# MiniRelay.net
KiCad netlist of a schematic drawn in Altium Designer
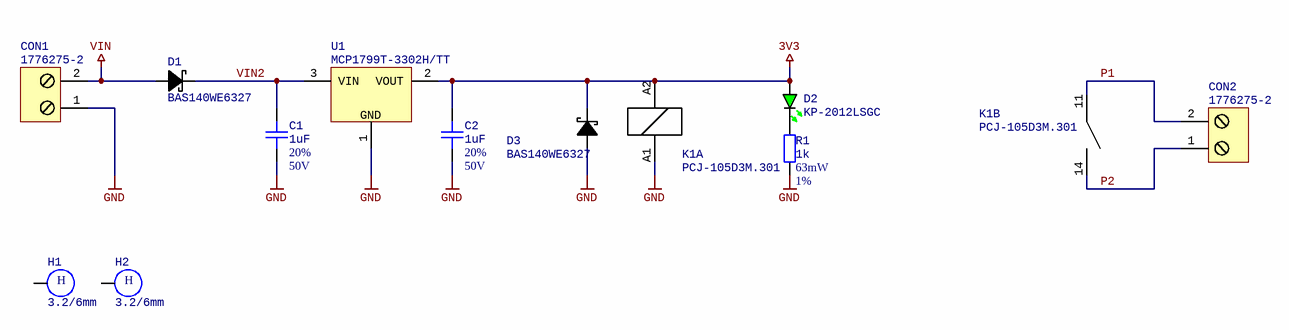
[diagram p0: MiniRelay.SchDoc]

(export (version "E")
  (design (tool "Eeschema 10.0.6"))
  (components
    (comp (ref "C1")
      (value "1uF")
      (footprint "CAP0805")
      (description "Capacitor")
      (fields (field (name "TOLERANCE") "20%") (field (name "VOLTAGE") "50V"))
      (libsource (lib "capacitor") (part "Capacitor"))
    )
    (comp (ref "C2")
      (value "1uF")
      (footprint "CAP0805")
      (description "Capacitor")
      (fields (field (name "TOLERANCE") "20%") (field (name "VOLTAGE") "50V"))
      (libsource (lib "capacitor") (part "Capacitor"))
    )
    (comp (ref "CON1")
      (value "1776275-2")
      (footprint "Terminal-block-2way-5.0")
      (description "Screwed terminal block with 2 pins")
      (fields (field (name "MANUFACTURER") "TE Connectivity"))
      (libsource (lib "") (part "Terminal Block 2_1"))
    )
    (comp (ref "CON2")
      (value "1776275-2")
      (footprint "Terminal-block-2way-5.0")
      (description "Screwed terminal block with 2 pins")
      (fields (field (name "MANUFACTURER") "TE Connectivity"))
      (libsource (lib "connector") (part "Terminal Block 2"))
    )
    (comp (ref "D1")
      (value "BAS140WE6327")
      (footprint "SOD323")
      (description "Silicon Schottky Diode. General-purpose diode for high-speed switching")
      (fields (field (name "MANUFACTURER") "Infineon"))
      (libsource (lib "diode") (part "BAS140W"))
    )
    (comp (ref "D2")
      (value "KP-2012LSGC")
      (footprint "0805_LED_GRN")
      (description "LED; SMD; 0805; green; 0.2÷0.5mcd; 2x1.25x1.1mm; 160°; 1.9÷2.25V")
      (fields (field (name "MANUFACTURER") "KINGBRIGHT ELECTRONIC"))
      (libsource (lib "diode") (part "KP-2012LSGC"))
    )
    (comp (ref "D3")
      (value "BAS140WE6327")
      (footprint "SOD323")
      (description "Silicon Schottky Diode. General-purpose diode for high-speed switching")
      (fields (field (name "MANUFACTURER") "Infineon"))
      (libsource (lib "diode") (part "BAS140W"))
    )
    (comp (ref "H1")
      (value "3.2/6mm")
      (footprint "Hole-3.2/0")
      (description "Generic hole component with 1 electrical connection")
      (libsource (lib "hole") (part "hole_metalized"))
    )
    (comp (ref "H2")
      (value "3.2/6mm")
      (footprint "Hole-3.2/0")
      (description "Generic hole component with 1 electrical connection")
      (libsource (lib "hole") (part "hole_metalized"))
    )
    (comp (ref "K1")
      (value "PCJ-105D3M.301")
      (footprint "1721081-2")
      (description "Miniature PCB Relay PCJ")
      (fields (field (name "MANUFACTURER") "TE Connectivity"))
      (libsource (lib "relay") (part "PCJ-1xxD3M.301"))
    )
    (comp (ref "R1")
      (value "1k")
      (footprint "RES0603")
      (description "Generic resistor symbol")
      (fields (field (name "POWER") "63mW") (field (name "TOLERANCE") "1%"))
      (libsource (lib "resistor") (part "Resistor"))
    )
    (comp (ref "U1")
      (value "MCP1799T-3302H/TT")
      (footprint "SOT23-3L")
      (description "IC: voltage regulator; LDO,linear,fixed; 3.3V/5V; 80mA; SOT23; SMD")
      (fields (field (name "MANUFACTURER") "Microchip"))
      (libsource (lib "converter") (part "MCP1799T-xx02H/TT"))
    )
  )
  (nets
    (net (code "1") (name "/P1") (class "Default")
      (node (ref "CON2") (pin "2") (pinfunction "2_2") (pintype "passive"))
      (node (ref "K1") (pin "11") (pinfunction "11_11") (pintype "passive"))
    )
    (net (code "2") (name "/P2") (class "Default")
      (node (ref "CON2") (pin "1") (pinfunction "1_1") (pintype "passive"))
      (node (ref "K1") (pin "14") (pinfunction "14_14") (pintype "passive"))
    )
    (net (code "3") (name "/VIN2") (class "Default")
      (node (ref "C1") (pin "1") (pinfunction "1_1") (pintype "passive"))
      (node (ref "D1") (pin "1") (pinfunction "K_1") (pintype "passive"))
      (node (ref "U1") (pin "3") (pinfunction "VIN_3") (pintype "power_in"))
    )
    (net (code "4") (name "3V3") (class "Default")
      (node (ref "C2") (pin "1") (pinfunction "1_1") (pintype "passive"))
      (node (ref "D2") (pin "2") (pinfunction "A_2") (pintype "passive"))
      (node (ref "D3") (pin "1") (pinfunction "K_1") (pintype "passive"))
      (node (ref "K1") (pin "A2") (pinfunction "A2_A2") (pintype "passive"))
      (node (ref "U1") (pin "2") (pinfunction "VOUT_2") (pintype "power_in"))
    )
    (net (code "5") (name "GND") (class "Default")
      (node (ref "C1") (pin "2") (pinfunction "2_2") (pintype "passive"))
      (node (ref "C2") (pin "2") (pinfunction "2_2") (pintype "passive"))
      (node (ref "CON1") (pin "1") (pinfunction "1_1") (pintype "passive"))
      (node (ref "D3") (pin "2") (pinfunction "A_2") (pintype "passive"))
      (node (ref "K1") (pin "A1") (pinfunction "A1_A1") (pintype "passive"))
      (node (ref "R1") (pin "1") (pinfunction "1_1") (pintype "passive"))
      (node (ref "U1") (pin "1") (pinfunction "GND_1") (pintype "power_in"))
    )
    (net (code "6") (name "Net-(D2-K)") (class "Default")
      (node (ref "D2") (pin "1") (pinfunction "K_1") (pintype "passive"))
      (node (ref "R1") (pin "2") (pinfunction "2_2") (pintype "passive"))
    )
    (net (code "7") (name "VIN") (class "Default")
      (node (ref "CON1") (pin "2") (pinfunction "2_2") (pintype "passive"))
      (node (ref "D1") (pin "2") (pinfunction "A_2") (pintype "passive"))
    )
    (net (code "8") (name "unconnected-(H1-Pad1)") (class "Default")
      (node (ref "H1") (pin "1") (pinfunction "1_1") (pintype "passive"))
    )
    (net (code "9") (name "unconnected-(H2-Pad1)") (class "Default")
      (node (ref "H2") (pin "1") (pinfunction "1_1") (pintype "passive"))
    )
  )
)
